# MCU.net
KiCad netlist of a schematic drawn in Altium Designer
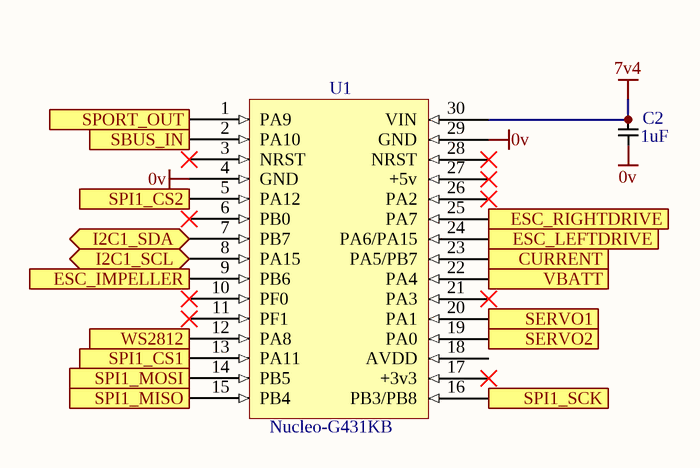
[diagram p0: MCU.SchDoc]

(export (version "E")
  (design (tool "Eeschema 10.0.6"))
  (components
    (comp (ref "C2") (value "1uF") (footprint "0805") (libsource (lib "Parts") (part "Capacitor")))
    (comp (ref "U1")
      (value "Nucleo-G431KB")
      (footprint "nucleo")
      (libsource (lib "Parts") (part "Nucleo-G431KB"))
    )
  )
  (nets
    (net (code "1") (name "/CURRENT") (class "Default")
      (node (ref "U1") (pin "23") (pinfunction "PA5/PB7_23") (pintype "input"))
    )
    (net (code "2") (name "/ESC_IMPELLER") (class "Default")
      (node (ref "U1") (pin "9") (pinfunction "PB6_9") (pintype "input"))
    )
    (net (code "3") (name "/ESC_LEFTDRIVE") (class "Default")
      (node (ref "U1") (pin "24") (pinfunction "PA6/PA15_24") (pintype "input"))
    )
    (net (code "4") (name "/ESC_RIGHTDRIVE") (class "Default")
      (node (ref "U1") (pin "25") (pinfunction "PA7_25") (pintype "input"))
    )
    (net (code "5") (name "/I2C1_SCL") (class "Default")
      (node (ref "U1") (pin "8") (pinfunction "PA15_8") (pintype "input"))
    )
    (net (code "6") (name "/I2C1_SDA") (class "Default")
      (node (ref "U1") (pin "7") (pinfunction "PB7_7") (pintype "input"))
    )
    (net (code "7") (name "/SBUS_IN") (class "Default")
      (node (ref "U1") (pin "2") (pinfunction "PA10_2") (pintype "input"))
    )
    (net (code "8") (name "/SERVO1") (class "Default")
      (node (ref "U1") (pin "20") (pinfunction "PA1_20") (pintype "input"))
    )
    (net (code "9") (name "/SERVO2") (class "Default")
      (node (ref "U1") (pin "19") (pinfunction "PA0_19") (pintype "input"))
    )
    (net (code "10") (name "/SPI1_CS1") (class "Default")
      (node (ref "U1") (pin "13") (pinfunction "PA11_13") (pintype "input"))
    )
    (net (code "11") (name "/SPI1_CS2") (class "Default")
      (node (ref "U1") (pin "5") (pinfunction "PA12_5") (pintype "input"))
    )
    (net (code "12") (name "/SPI1_MISO") (class "Default")
      (node (ref "U1") (pin "15") (pinfunction "PB4_15") (pintype "input"))
    )
    (net (code "13") (name "/SPI1_MOSI") (class "Default")
      (node (ref "U1") (pin "14") (pinfunction "PB5_14") (pintype "input"))
    )
    (net (code "14") (name "/SPI1_SCK") (class "Default")
      (node (ref "U1") (pin "16") (pinfunction "PB3/PB8_16") (pintype "input"))
    )
    (net (code "15") (name "/SPORT_OUT") (class "Default")
      (node (ref "U1") (pin "1") (pinfunction "PA9_1") (pintype "input"))
    )
    (net (code "16") (name "/VBATT") (class "Default")
      (node (ref "U1") (pin "22") (pinfunction "PA4_22") (pintype "input"))
    )
    (net (code "17") (name "/WS2812") (class "Default")
      (node (ref "U1") (pin "12") (pinfunction "PA8_12") (pintype "input"))
    )
    (net (code "18") (name "0v") (class "Default")
      (node (ref "C2") (pin "2") (pinfunction "1_2") (pintype "passive"))
      (node (ref "U1") (pin "29") (pinfunction "GND_29") (pintype "input"))
      (node (ref "U1") (pin "4") (pinfunction "GND_4") (pintype "input"))
    )
    (net (code "19") (name "7v4") (class "Default")
      (node (ref "C2") (pin "1") (pinfunction "0_1") (pintype "passive"))
      (node (ref "U1") (pin "30") (pinfunction "VIN_30") (pintype "input"))
    )
    (net (code "20") (name "unconnected-(U1-+3v3-Pad17)") (class "Default")
      (node (ref "U1") (pin "17") (pinfunction "+3v3_17") (pintype "input+no_connect"))
    )
    (net (code "21") (name "unconnected-(U1-+5v-Pad27)") (class "Default")
      (node (ref "U1") (pin "27") (pinfunction "+5v_27") (pintype "input+no_connect"))
    )
    (net (code "22") (name "unconnected-(U1-AVDD-Pad18)") (class "Default")
      (node (ref "U1") (pin "18") (pinfunction "AVDD_18") (pintype "input"))
    )
    (net (code "23") (name "unconnected-(U1-NRST-Pad3)") (class "Default")
      (node (ref "U1") (pin "3") (pinfunction "NRST_3") (pintype "input+no_connect"))
    )
    (net (code "24") (name "unconnected-(U1-NRST-Pad28)") (class "Default")
      (node (ref "U1") (pin "28") (pinfunction "NRST_28") (pintype "input+no_connect"))
    )
    (net (code "25") (name "unconnected-(U1-PA2-Pad26)") (class "Default")
      (node (ref "U1") (pin "26") (pinfunction "PA2_26") (pintype "input+no_connect"))
    )
    (net (code "26") (name "unconnected-(U1-PA3-Pad21)") (class "Default")
      (node (ref "U1") (pin "21") (pinfunction "PA3_21") (pintype "input+no_connect"))
    )
    (net (code "27") (name "unconnected-(U1-PB0-Pad6)") (class "Default")
      (node (ref "U1") (pin "6") (pinfunction "PB0_6") (pintype "input+no_connect"))
    )
    (net (code "28") (name "unconnected-(U1-PF0-Pad10)") (class "Default")
      (node (ref "U1") (pin "10") (pinfunction "PF0_10") (pintype "input+no_connect"))
    )
    (net (code "29") (name "unconnected-(U1-PF1-Pad11)") (class "Default")
      (node (ref "U1") (pin "11") (pinfunction "PF1_11") (pintype "input+no_connect"))
    )
  )
)
